# JTAG_Configuration.net
KiCad netlist of a schematic drawn in Altium Designer
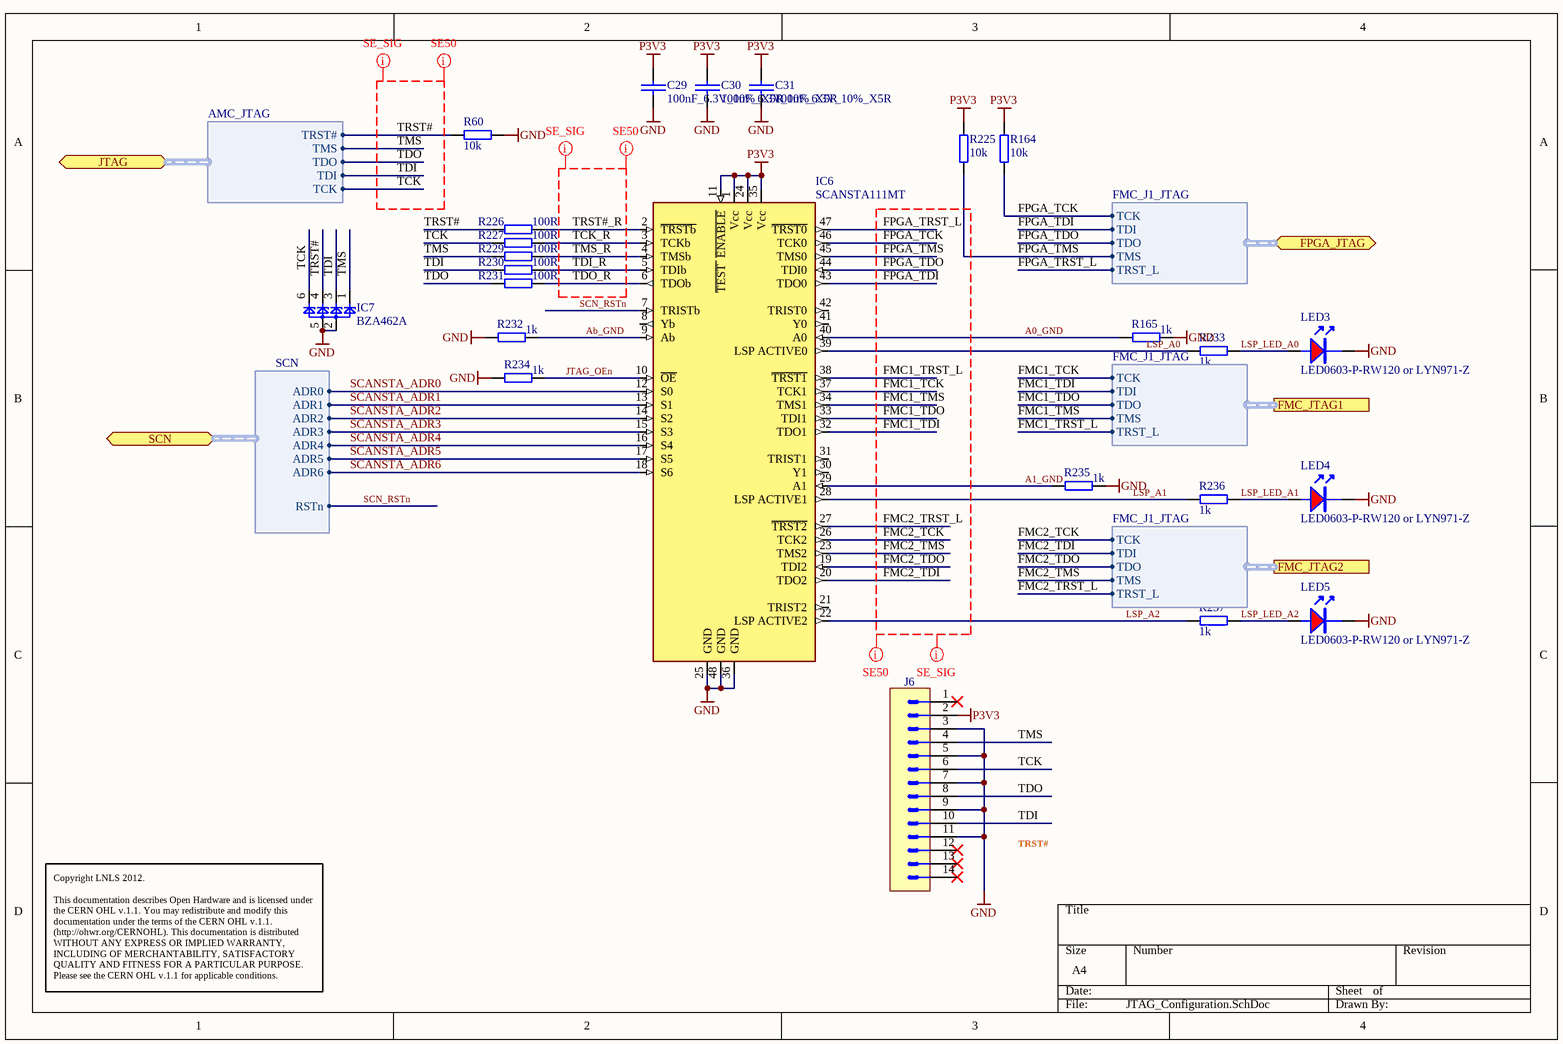
[diagram p0: JTAG_Configuration.SchDoc]

(export (version "E")
  (design (tool "Eeschema 10.0.6"))
  (components
    (comp (ref "C29")
      (value "100nF_6.3V_10%_X5R")
      (footprint "0201C")
      (description "Capacitor SMD")
      (libsource (lib "LIBRARY_SCH") (part "CAP_SMD_0201"))
    )
    (comp (ref "C30")
      (value "100nF_6.3V_10%_X5R")
      (footprint "0201C")
      (description "Capacitor SMD")
      (libsource (lib "LIBRARY_SCH") (part "CAP_SMD_0201"))
    )
    (comp (ref "C31")
      (value "100nF_6.3V_10%_X5R")
      (footprint "0201C")
      (description "Capacitor SMD")
      (libsource (lib "LIBRARY_SCH") (part "CAP_SMD_0201"))
    )
    (comp (ref "IC6")
      (value "SCANSTA111MT")
      (footprint "TSSOP-48")
      (description "Enhanced SCAN Bridge Multidrop Addressable IEEE 1149.1 (JTAG) Port")
      (libsource (lib "LIBRARY_SCH") (part "IFC_SCANSTA111"))
    )
    (comp (ref "IC7")
      (value "BZA462A")
      (footprint "SOT23-6")
      (description "Quadruple 4V ESD transient voltage suppressor")
      (libsource (lib "LIBRARY_SCH") (part "D_TVS_BZA462A"))
    )
    (comp (ref "J6")
      (value "BHMT14S")
      (footprint "BHMT14S")
      (description "Connector 14 Male")
      (fields (field (name "AUTHOR") "CERN DEM JLC"))
      (libsource (lib "Connectors") (part "Connector 14 Male"))
    )
    (comp (ref "LED3")
      (value "LED0603-P-RW120 or LYN971-Z")
      (footprint "led_0603R")
      (description "LED 0603 red")
      (libsource (lib "LIBRARY_SCH") (part "LED_0603R"))
    )
    (comp (ref "LED4")
      (value "LED0603-P-RW120 or LYN971-Z")
      (footprint "led_0603R")
      (description "LED 0603 red")
      (libsource (lib "LIBRARY_SCH") (part "LED_0603R"))
    )
    (comp (ref "LED5")
      (value "LED0603-P-RW120 or LYN971-Z")
      (footprint "led_0603R")
      (description "LED 0603 red")
      (libsource (lib "LIBRARY_SCH") (part "LED_0603R"))
    )
    (comp (ref "R60")
      (value "10k")
      (footprint "0402R")
      (description "SMD Resistor")
      (libsource (lib "LIBRARY_SCH") (part "RES_0402"))
    )
    (comp (ref "R164")
      (value "10k")
      (footprint "0402R")
      (description "SMD Resistor")
      (libsource (lib "LIBRARY_SCH") (part "RES_0402"))
    )
    (comp (ref "R165")
      (value "1k")
      (footprint "0402R")
      (description "SMD Resistor")
      (libsource (lib "LIBRARY_SCH") (part "RES_0402"))
    )
    (comp (ref "R225")
      (value "10k")
      (footprint "0402R")
      (description "SMD Resistor")
      (libsource (lib "LIBRARY_SCH") (part "RES_0402"))
    )
    (comp (ref "R226")
      (value "100R")
      (footprint "0402R")
      (description "SMD Resistor")
      (libsource (lib "LIBRARY_SCH") (part "RES_0402"))
    )
    (comp (ref "R227")
      (value "100R")
      (footprint "0402R")
      (description "SMD Resistor")
      (libsource (lib "LIBRARY_SCH") (part "RES_0402"))
    )
    (comp (ref "R229")
      (value "100R")
      (footprint "0402R")
      (description "SMD Resistor")
      (libsource (lib "LIBRARY_SCH") (part "RES_0402"))
    )
    (comp (ref "R230")
      (value "100R")
      (footprint "0402R")
      (description "SMD Resistor")
      (libsource (lib "LIBRARY_SCH") (part "RES_0402"))
    )
    (comp (ref "R231")
      (value "100R")
      (footprint "0402R")
      (description "SMD Resistor")
      (libsource (lib "LIBRARY_SCH") (part "RES_0402"))
    )
    (comp (ref "R232")
      (value "1k")
      (footprint "0402R")
      (description "SMD Resistor")
      (libsource (lib "LIBRARY_SCH") (part "RES_0402"))
    )
    (comp (ref "R233")
      (value "1k")
      (footprint "0402R")
      (description "SMD Resistor")
      (libsource (lib "LIBRARY_SCH") (part "RES_0402"))
    )
    (comp (ref "R234")
      (value "1k")
      (footprint "0402R")
      (description "SMD Resistor")
      (libsource (lib "LIBRARY_SCH") (part "RES_0402"))
    )
    (comp (ref "R235")
      (value "1k")
      (footprint "0402R")
      (description "SMD Resistor")
      (libsource (lib "LIBRARY_SCH") (part "RES_0402"))
    )
    (comp (ref "R236")
      (value "1k")
      (footprint "0402R")
      (description "SMD Resistor")
      (libsource (lib "LIBRARY_SCH") (part "RES_0402"))
    )
    (comp (ref "R237")
      (value "1k")
      (footprint "0402R")
      (description "SMD Resistor")
      (libsource (lib "LIBRARY_SCH") (part "RES_0402"))
    )
  )
  (nets
    (net (code "4") (name "/A0_GND") (class "Default")
      (node (ref "IC6") (pin "40") (pinfunction "A0_40") (pintype "input"))
      (node (ref "R165") (pin "1") (pinfunction "1_1") (pintype "passive"))
    )
    (net (code "5") (name "/A1_GND") (class "Default")
      (node (ref "IC6") (pin "29") (pinfunction "A1_29") (pintype "input"))
      (node (ref "R235") (pin "1") (pinfunction "1_1") (pintype "passive"))
    )
    (net (code "6") (name "/Ab_GND") (class "Default")
      (node (ref "IC6") (pin "9") (pinfunction "Ab_9") (pintype "input"))
      (node (ref "R232") (pin "2") (pinfunction "2_2") (pintype "passive"))
    )
    (net (code "7") (name "/FMC1_TCK") (class "Default")
      (node (ref "IC6") (pin "37") (pinfunction "TCK1_37") (pintype "output"))
    )
    (net (code "8") (name "/FMC1_TDI") (class "Default")
      (node (ref "IC6") (pin "32") (pinfunction "TDO1_32") (pintype "output"))
    )
    (net (code "9") (name "/FMC1_TDO") (class "Default")
      (node (ref "IC6") (pin "33") (pinfunction "TDI1_33") (pintype "output"))
    )
    (net (code "10") (name "/FMC1_TMS") (class "Default")
      (node (ref "IC6") (pin "34") (pinfunction "TMS1_34") (pintype "output"))
    )
    (net (code "11") (name "/FMC1_TRST_L") (class "Default")
      (node (ref "IC6") (pin "38") (pinfunction "~{TRST1}_38") (pintype "output"))
    )
    (net (code "12") (name "/FMC2_TCK") (class "Default")
      (node (ref "IC6") (pin "26") (pinfunction "TCK2_26") (pintype "output"))
    )
    (net (code "13") (name "/FMC2_TDI") (class "Default")
      (node (ref "IC6") (pin "20") (pinfunction "TDO2_20") (pintype "output"))
    )
    (net (code "14") (name "/FMC2_TDO") (class "Default")
      (node (ref "IC6") (pin "19") (pinfunction "TDI2_19") (pintype "input"))
    )
    (net (code "15") (name "/FMC2_TMS") (class "Default")
      (node (ref "IC6") (pin "23") (pinfunction "TMS2_23") (pintype "output"))
    )
    (net (code "16") (name "/FMC2_TRST_L") (class "Default")
      (node (ref "IC6") (pin "27") (pinfunction "~{TRST2}_27") (pintype "output"))
    )
    (net (code "17") (name "/FPGA_TCK") (class "Default")
      (node (ref "IC6") (pin "46") (pinfunction "TCK0_46") (pintype "output"))
      (node (ref "R164") (pin "1") (pinfunction "1_1") (pintype "passive"))
    )
    (net (code "18") (name "/FPGA_TDI") (class "Default")
      (node (ref "IC6") (pin "43") (pinfunction "TDO0_43") (pintype "output"))
    )
    (net (code "19") (name "/FPGA_TDO") (class "Default")
      (node (ref "IC6") (pin "44") (pinfunction "TDI0_44") (pintype "input"))
    )
    (net (code "20") (name "/FPGA_TMS") (class "Default")
      (node (ref "IC6") (pin "45") (pinfunction "TMS0_45") (pintype "output"))
      (node (ref "R225") (pin "1") (pinfunction "1_1") (pintype "passive"))
    )
    (net (code "21") (name "/FPGA_TRST_L") (class "Default")
      (node (ref "IC6") (pin "47") (pinfunction "~{TRST0}_47") (pintype "output"))
    )
    (net (code "22") (name "/JTAG_OEn") (class "Default")
      (node (ref "IC6") (pin "10") (pinfunction "~{OE}_10") (pintype "input"))
      (node (ref "R234") (pin "2") (pinfunction "2_2") (pintype "passive"))
    )
    (net (code "23") (name "/LSP_A0") (class "Default")
      (node (ref "IC6") (pin "39") (pinfunction "LSP_ACTIVE0_39") (pintype "output"))
      (node (ref "R233") (pin "1") (pinfunction "1_1") (pintype "passive"))
    )
    (net (code "24") (name "/LSP_A1") (class "Default")
      (node (ref "IC6") (pin "28") (pinfunction "LSP_ACTIVE1_28") (pintype "output"))
      (node (ref "R236") (pin "1") (pinfunction "1_1") (pintype "passive"))
    )
    (net (code "25") (name "/LSP_A2") (class "Default")
      (node (ref "IC6") (pin "22") (pinfunction "LSP_ACTIVE2_22") (pintype "output"))
      (node (ref "R237") (pin "1") (pinfunction "1_1") (pintype "passive"))
    )
    (net (code "26") (name "/LSP_LED_A0") (class "Default")
      (node (ref "LED3") (pin "A") (pinfunction "A_A") (pintype "passive"))
      (node (ref "R233") (pin "2") (pinfunction "2_2") (pintype "passive"))
    )
    (net (code "27") (name "/LSP_LED_A1") (class "Default")
      (node (ref "LED4") (pin "A") (pinfunction "A_A") (pintype "passive"))
      (node (ref "R236") (pin "2") (pinfunction "2_2") (pintype "passive"))
    )
    (net (code "28") (name "/LSP_LED_A2") (class "Default")
      (node (ref "LED5") (pin "A") (pinfunction "A_A") (pintype "passive"))
      (node (ref "R237") (pin "2") (pinfunction "2_2") (pintype "passive"))
    )
    (net (code "29") (name "/SCANSTA_ADR0") (class "Default")
      (node (ref "IC6") (pin "12") (pinfunction "S0_12") (pintype "input"))
    )
    (net (code "30") (name "/SCANSTA_ADR1") (class "Default")
      (node (ref "IC6") (pin "13") (pinfunction "S1_13") (pintype "input"))
    )
    (net (code "31") (name "/SCANSTA_ADR2") (class "Default")
      (node (ref "IC6") (pin "14") (pinfunction "S2_14") (pintype "input"))
    )
    (net (code "32") (name "/SCANSTA_ADR3") (class "Default")
      (node (ref "IC6") (pin "15") (pinfunction "S3_15") (pintype "input"))
    )
    (net (code "33") (name "/SCANSTA_ADR4") (class "Default")
      (node (ref "IC6") (pin "16") (pinfunction "S4_16") (pintype "input"))
    )
    (net (code "34") (name "/SCANSTA_ADR5") (class "Default")
      (node (ref "IC6") (pin "17") (pinfunction "S5_17") (pintype "input"))
    )
    (net (code "35") (name "/SCANSTA_ADR6") (class "Default")
      (node (ref "IC6") (pin "18") (pinfunction "S6_18") (pintype "input"))
    )
    (net (code "36") (name "/SCN_RSTn") (class "Default")
      (node (ref "IC6") (pin "7") (pinfunction "TRISTb_7") (pintype "input"))
    )
    (net (code "37") (name "/TCK") (class "Default")
      (node (ref "IC7") (pin "6") (pinfunction "6_6") (pintype "passive"))
      (node (ref "J6") (pin "6") (pinfunction "6_6") (pintype "passive"))
      (node (ref "R227") (pin "1") (pinfunction "1_1") (pintype "passive"))
    )
    (net (code "38") (name "/TCK_R") (class "Default")
      (node (ref "IC6") (pin "3") (pinfunction "TCKb_3") (pintype "input"))
      (node (ref "R227") (pin "2") (pinfunction "2_2") (pintype "passive"))
    )
    (net (code "39") (name "/TDI") (class "Default")
      (node (ref "IC7") (pin "3") (pinfunction "3_3") (pintype "passive"))
      (node (ref "J6") (pin "10") (pinfunction "10_10") (pintype "passive"))
      (node (ref "R230") (pin "1") (pinfunction "1_1") (pintype "passive"))
    )
    (net (code "40") (name "/TDI_R") (class "Default")
      (node (ref "IC6") (pin "5") (pinfunction "TDIb_5") (pintype "input"))
      (node (ref "R230") (pin "2") (pinfunction "2_2") (pintype "passive"))
    )
    (net (code "41") (name "/TDO") (class "Default")
      (node (ref "J6") (pin "8") (pinfunction "8_8") (pintype "passive"))
      (node (ref "R231") (pin "1") (pinfunction "1_1") (pintype "passive"))
    )
    (net (code "42") (name "/TDO_R") (class "Default")
      (node (ref "IC6") (pin "6") (pinfunction "TDOb_6") (pintype "output"))
      (node (ref "R231") (pin "2") (pinfunction "2_2") (pintype "passive"))
    )
    (net (code "43") (name "/TMS") (class "Default")
      (node (ref "IC7") (pin "1") (pinfunction "1_1") (pintype "passive"))
      (node (ref "J6") (pin "4") (pinfunction "4_4") (pintype "passive"))
      (node (ref "R229") (pin "1") (pinfunction "1_1") (pintype "passive"))
    )
    (net (code "44") (name "/TMS_R") (class "Default")
      (node (ref "IC6") (pin "4") (pinfunction "TMSb_4") (pintype "input"))
      (node (ref "R229") (pin "2") (pinfunction "2_2") (pintype "passive"))
    )
    (net (code "45") (name "/TRST#") (class "Default")
      (node (ref "IC7") (pin "4") (pinfunction "4_4") (pintype "passive"))
      (node (ref "R226") (pin "1") (pinfunction "1_1") (pintype "passive"))
      (node (ref "R60") (pin "2") (pinfunction "2_2") (pintype "passive"))
    )
    (net (code "46") (name "/TRST#_R") (class "Default")
      (node (ref "IC6") (pin "2") (pinfunction "~{TRSTb}_2") (pintype "input"))
      (node (ref "R226") (pin "2") (pinfunction "2_2") (pintype "passive"))
    )
    (net (code "50") (name "GND") (class "Default")
      (node (ref "C29") (pin "2") (pinfunction "2_2") (pintype "passive"))
      (node (ref "C30") (pin "2") (pinfunction "2_2") (pintype "passive"))
      (node (ref "C31") (pin "2") (pinfunction "2_2") (pintype "passive"))
      (node (ref "IC6") (pin "25") (pinfunction "GND_25") (pintype "power_in"))
      (node (ref "IC6") (pin "36") (pinfunction "GND_36") (pintype "power_in"))
      (node (ref "IC6") (pin "48") (pinfunction "GND_48") (pintype "power_in"))
      (node (ref "IC7") (pin "2") (pinfunction "2_2") (pintype "passive"))
      (node (ref "IC7") (pin "5") (pinfunction "5_5") (pintype "passive"))
      (node (ref "J6") (pin "11") (pinfunction "11_11") (pintype "passive"))
      (node (ref "J6") (pin "3") (pinfunction "3_3") (pintype "passive"))
      (node (ref "J6") (pin "5") (pinfunction "5_5") (pintype "passive"))
      (node (ref "J6") (pin "7") (pinfunction "7_7") (pintype "passive"))
      (node (ref "J6") (pin "9") (pinfunction "9_9") (pintype "passive"))
      (node (ref "LED3") (pin "K") (pinfunction "K_K") (pintype "passive"))
      (node (ref "LED4") (pin "K") (pinfunction "K_K") (pintype "passive"))
      (node (ref "LED5") (pin "K") (pinfunction "K_K") (pintype "passive"))
      (node (ref "R165") (pin "2") (pinfunction "2_2") (pintype "passive"))
      (node (ref "R232") (pin "1") (pinfunction "1_1") (pintype "passive"))
      (node (ref "R234") (pin "1") (pinfunction "1_1") (pintype "passive"))
      (node (ref "R235") (pin "2") (pinfunction "2_2") (pintype "passive"))
      (node (ref "R60") (pin "1") (pinfunction "1_1") (pintype "passive"))
    )
    (net (code "51") (name "P3V3") (class "Default")
      (node (ref "C29") (pin "1") (pinfunction "1_1") (pintype "passive"))
      (node (ref "C30") (pin "1") (pinfunction "1_1") (pintype "passive"))
      (node (ref "C31") (pin "1") (pinfunction "1_1") (pintype "passive"))
      (node (ref "IC6") (pin "1") (pinfunction "Vcc_1") (pintype "power_in"))
      (node (ref "IC6") (pin "11") (pinfunction "~{TEST_}_~{ENABLE}_11") (pintype "input"))
      (node (ref "IC6") (pin "24") (pinfunction "Vcc_24") (pintype "power_in"))
      (node (ref "IC6") (pin "35") (pinfunction "Vcc_35") (pintype "power_in"))
      (node (ref "J6") (pin "2") (pinfunction "2_2") (pintype "passive"))
      (node (ref "R164") (pin "2") (pinfunction "2_2") (pintype "passive"))
      (node (ref "R225") (pin "2") (pinfunction "2_2") (pintype "passive"))
    )
    (net (code "52") (name "unconnected-(IC6-TRIST0-Pad42)") (class "Default")
      (node (ref "IC6") (pin "42") (pinfunction "TRIST0_42") (pintype "output"))
    )
    (net (code "53") (name "unconnected-(IC6-TRIST1-Pad31)") (class "Default")
      (node (ref "IC6") (pin "31") (pinfunction "TRIST1_31") (pintype "output"))
    )
    (net (code "54") (name "unconnected-(IC6-TRIST2-Pad21)") (class "Default")
      (node (ref "IC6") (pin "21") (pinfunction "TRIST2_21") (pintype "output"))
    )
    (net (code "55") (name "unconnected-(IC6-Y0-Pad41)") (class "Default")
      (node (ref "IC6") (pin "41") (pinfunction "Y0_41") (pintype "output"))
    )
    (net (code "56") (name "unconnected-(IC6-Y1-Pad30)") (class "Default")
      (node (ref "IC6") (pin "30") (pinfunction "Y1_30") (pintype "output"))
    )
    (net (code "57") (name "unconnected-(IC6-Yb-Pad8)") (class "Default")
      (node (ref "IC6") (pin "8") (pinfunction "Yb_8") (pintype "output"))
    )
    (net (code "58") (name "unconnected-(J6-Pad1)") (class "Default")
      (node (ref "J6") (pin "1") (pinfunction "1_1") (pintype "passive+no_connect"))
    )
    (net (code "59") (name "unconnected-(J6-Pad12)") (class "Default")
      (node (ref "J6") (pin "12") (pinfunction "12_12") (pintype "passive+no_connect"))
    )
    (net (code "60") (name "unconnected-(J6-Pad13)") (class "Default")
      (node (ref "J6") (pin "13") (pinfunction "13_13") (pintype "passive+no_connect"))
    )
    (net (code "61") (name "unconnected-(J6-Pad14)") (class "Default")
      (node (ref "J6") (pin "14") (pinfunction "14_14") (pintype "passive+no_connect"))
    )
  )
)
